# 04-GPS.net
KiCad netlist of a schematic drawn in Altium Designer
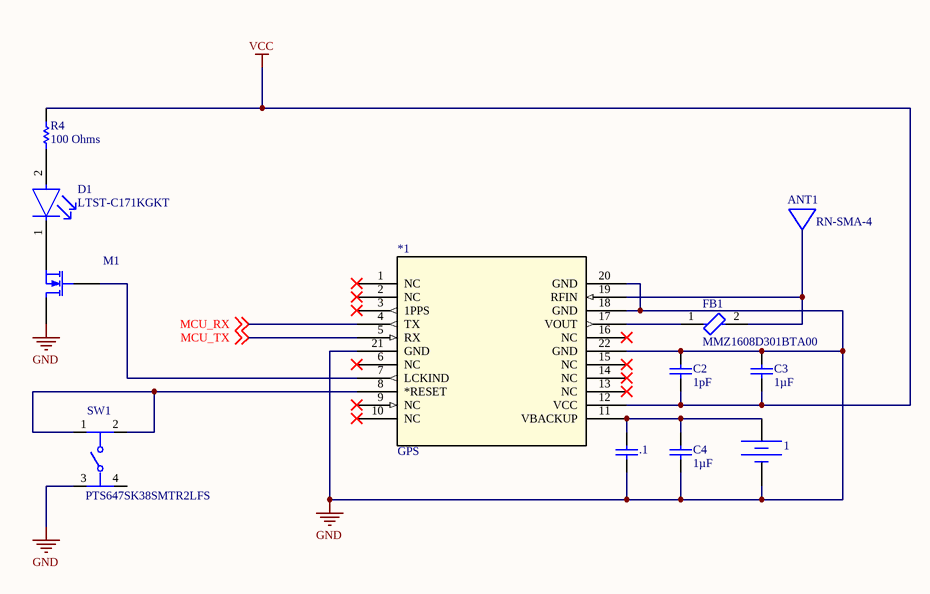
[diagram p0: 04-GPS.SchDoc]

(export (version "E")
  (design (tool "Eeschema 10.0.6"))
  (components
    (comp (ref "*1") (value "GPS") (libsource (lib "ECE453-F22-Power") (part "GPS")))
    (comp (ref ".1") (value "Capacitor") (libsource (lib "Simulation Generic Components") (part "Capacitor")))
    (comp (ref "1")
      (value "Constant Voltage Source")
      (libsource (lib "Simulation Generic Components") (part "Battery"))
    )
    (comp (ref "ANT1")
      (value "RN-SMA-4")
      (footprint "FP-RN-SMA-4-MFG")
      (description "RF ANT 2.4GHZ WHIP SMA MALE 4\"")
      (libsource (lib "Altium Content Vault") (part "2df8bb4c3baa31cb0e521f1ad81b276"))
    )
    (comp (ref "C2")
      (value "1pF")
      (description "Capacitor")
      (libsource (lib "Simulation Generic Components") (part "Capacitor"))
    )
    (comp (ref "C3")
      (value "1µF")
      (description "Capacitor")
      (libsource (lib "Simulation Generic Components") (part "Capacitor"))
    )
    (comp (ref "C4")
      (value "1µF")
      (description "Capacitor")
      (libsource (lib "Simulation Generic Components") (part "Capacitor"))
    )
    (comp (ref "D1")
      (value "LTST-C171KGKT")
      (footprint "FP-LTST-C171KGKT-MFG")
      (description "LED GREEN CLEAR SMD")
      (libsource (lib "Altium Content Vault") (part "8706943c75ba83719d021d2fdc84c58"))
    )
    (comp (ref "FB1")
      (value "MMZ1608D301BTA00")
      (footprint "FP-MMZ1608-0_8-MFG")
      (description "Signal Line Ferrite Bead 300Ω  @ 100MHz 300mA DCR 700mΩ SMD 0603")
      (libsource (lib "Altium Content Vault") (part "5f30dd21d616792df468990f7003faa"))
    )
    (comp (ref "M1")
      (value "N-chanel Power MOSFET VDMOS Model")
      (libsource (lib "Simulation Generic Components") (part "MOSFET P-ch VDMOS"))
    )
    (comp (ref "R4")
      (value "100 Ohms")
      (description "Resistor")
      (libsource (lib "Simulation Generic Components") (part "Resistor"))
    )
    (comp (ref "SW1")
      (value "PTS647SK38SMTR2LFS")
      (footprint "FP-PTS647SK38SMTR2LFS-MFG")
      (description "TACT 4.5 X 4.5, 3.8 MM H, 2.5N,")
      (libsource (lib "Altium Content Vault") (part "1adf0dd01260c80cf25a44bfd6b99ba"))
    )
  )
  (nets
    (net (code "1") (name "GND") (class "Default")
      (node (ref "*1") (pin "18") (pinfunction "GND_18") (pintype "passive"))
      (node (ref "*1") (pin "20") (pinfunction "GND_20") (pintype "passive"))
      (node (ref "*1") (pin "21") (pinfunction "GND_21") (pintype "passive"))
      (node (ref "*1") (pin "22") (pinfunction "GND_22") (pintype "passive"))
      (node (ref ".1") (pin "1") (pinfunction "1_1") (pintype "passive"))
      (node (ref "1") (pin "2") (pinfunction "2_2") (pintype "passive"))
      (node (ref "C2") (pin "2") (pinfunction "2_2") (pintype "passive"))
      (node (ref "C3") (pin "2") (pinfunction "2_2") (pintype "passive"))
      (node (ref "C4") (pin "1") (pinfunction "1_1") (pintype "passive"))
      (node (ref "M1") (pin "1") (pinfunction "D_1") (pintype "passive"))
      (node (ref "SW1") (pin "3") (pinfunction "3_3") (pintype "passive"))
    )
    (net (code "2") (name "MCU_RX") (class "Default")
      (node (ref "*1") (pin "4") (pinfunction "TX_4") (pintype "output"))
    )
    (net (code "3") (name "MCU_TX") (class "Default")
      (node (ref "*1") (pin "5") (pinfunction "RX_5") (pintype "input"))
    )
    (net (code "4") (name "Net-(*1-*RESET)") (class "Default")
      (node (ref "*1") (pin "8") (pinfunction "*RESET_8") (pintype "passive"))
      (node (ref "SW1") (pin "1") (pinfunction "1_1") (pintype "passive"))
      (node (ref "SW1") (pin "2") (pinfunction "2_2") (pintype "passive"))
    )
    (net (code "5") (name "Net-(*1-LCKIND)") (class "Default")
      (node (ref "*1") (pin "7") (pinfunction "LCKIND_7") (pintype "output"))
      (node (ref "M1") (pin "2") (pinfunction "G_2") (pintype "passive"))
    )
    (net (code "6") (name "Net-(*1-RFIN)") (class "Default")
      (node (ref "*1") (pin "19") (pinfunction "RFIN_19") (pintype "input"))
      (node (ref "FB1") (pin "2") (pinfunction "2_2") (pintype "passive"))
    )
    (net (code "7") (name "Net-(*1-VBACKUP)") (class "Default")
      (node (ref "*1") (pin "11") (pinfunction "VBACKUP_11") (pintype "power_in"))
      (node (ref ".1") (pin "2") (pinfunction "2_2") (pintype "passive"))
      (node (ref "1") (pin "1") (pinfunction "1_1") (pintype "passive"))
      (node (ref "C4") (pin "2") (pinfunction "2_2") (pintype "passive"))
    )
    (net (code "8") (name "Net-(*1-VOUT)") (class "Default")
      (node (ref "*1") (pin "17") (pinfunction "VOUT_17") (pintype "output"))
      (node (ref "FB1") (pin "1") (pinfunction "1_1") (pintype "passive"))
    )
    (net (code "9") (name "Net-(D1-A)") (class "Default")
      (node (ref "D1") (pin "2") (pinfunction "A_2") (pintype "passive"))
      (node (ref "R4") (pin "1") (pinfunction "1_1") (pintype "passive"))
    )
    (net (code "10") (name "Net-(D1-C)") (class "Default")
      (node (ref "D1") (pin "1") (pinfunction "C_1") (pintype "passive"))
      (node (ref "M1") (pin "3") (pinfunction "S_3") (pintype "passive"))
    )
    (net (code "11") (name "VCC") (class "Default")
      (node (ref "*1") (pin "12") (pinfunction "VCC_12") (pintype "power_in"))
      (node (ref "C2") (pin "1") (pinfunction "1_1") (pintype "passive"))
      (node (ref "C3") (pin "1") (pinfunction "1_1") (pintype "passive"))
      (node (ref "R4") (pin "2") (pinfunction "2_2") (pintype "passive"))
    )
    (net (code "12") (name "unconnected-(*1-1PPS-Pad3)") (class "Default")
      (node (ref "*1") (pin "3") (pinfunction "1PPS_3") (pintype "output+no_connect"))
    )
    (net (code "13") (name "unconnected-(*1-NC-Pad1)") (class "Default")
      (node (ref "*1") (pin "1") (pinfunction "NC_1") (pintype "passive+no_connect"))
    )
    (net (code "14") (name "unconnected-(*1-NC-Pad2)") (class "Default")
      (node (ref "*1") (pin "2") (pinfunction "NC_2") (pintype "passive+no_connect"))
    )
    (net (code "15") (name "unconnected-(*1-NC-Pad6)") (class "Default")
      (node (ref "*1") (pin "6") (pinfunction "NC_6") (pintype "passive+no_connect"))
    )
    (net (code "16") (name "unconnected-(*1-NC-Pad9)") (class "Default")
      (node (ref "*1") (pin "9") (pinfunction "NC_9") (pintype "input+no_connect"))
    )
    (net (code "17") (name "unconnected-(*1-NC-Pad10)") (class "Default")
      (node (ref "*1") (pin "10") (pinfunction "NC_10") (pintype "passive+no_connect"))
    )
    (net (code "18") (name "unconnected-(*1-NC-Pad13)") (class "Default")
      (node (ref "*1") (pin "13") (pinfunction "NC_13") (pintype "passive+no_connect"))
    )
    (net (code "19") (name "unconnected-(*1-NC-Pad14)") (class "Default")
      (node (ref "*1") (pin "14") (pinfunction "NC_14") (pintype "passive+no_connect"))
    )
    (net (code "20") (name "unconnected-(*1-NC-Pad15)") (class "Default")
      (node (ref "*1") (pin "15") (pinfunction "NC_15") (pintype "passive+no_connect"))
    )
    (net (code "21") (name "unconnected-(*1-NC-Pad16)") (class "Default")
      (node (ref "*1") (pin "16") (pinfunction "NC_16") (pintype "passive+no_connect"))
    )
    (net (code "22") (name "unconnected-(SW1-Pad4)") (class "Default")
      (node (ref "SW1") (pin "4") (pinfunction "4_4") (pintype "passive"))
    )
  )
)
